# ESP_LoRa_Thermal_V1_62.net
KiCad netlist of a schematic drawn in EAGLE
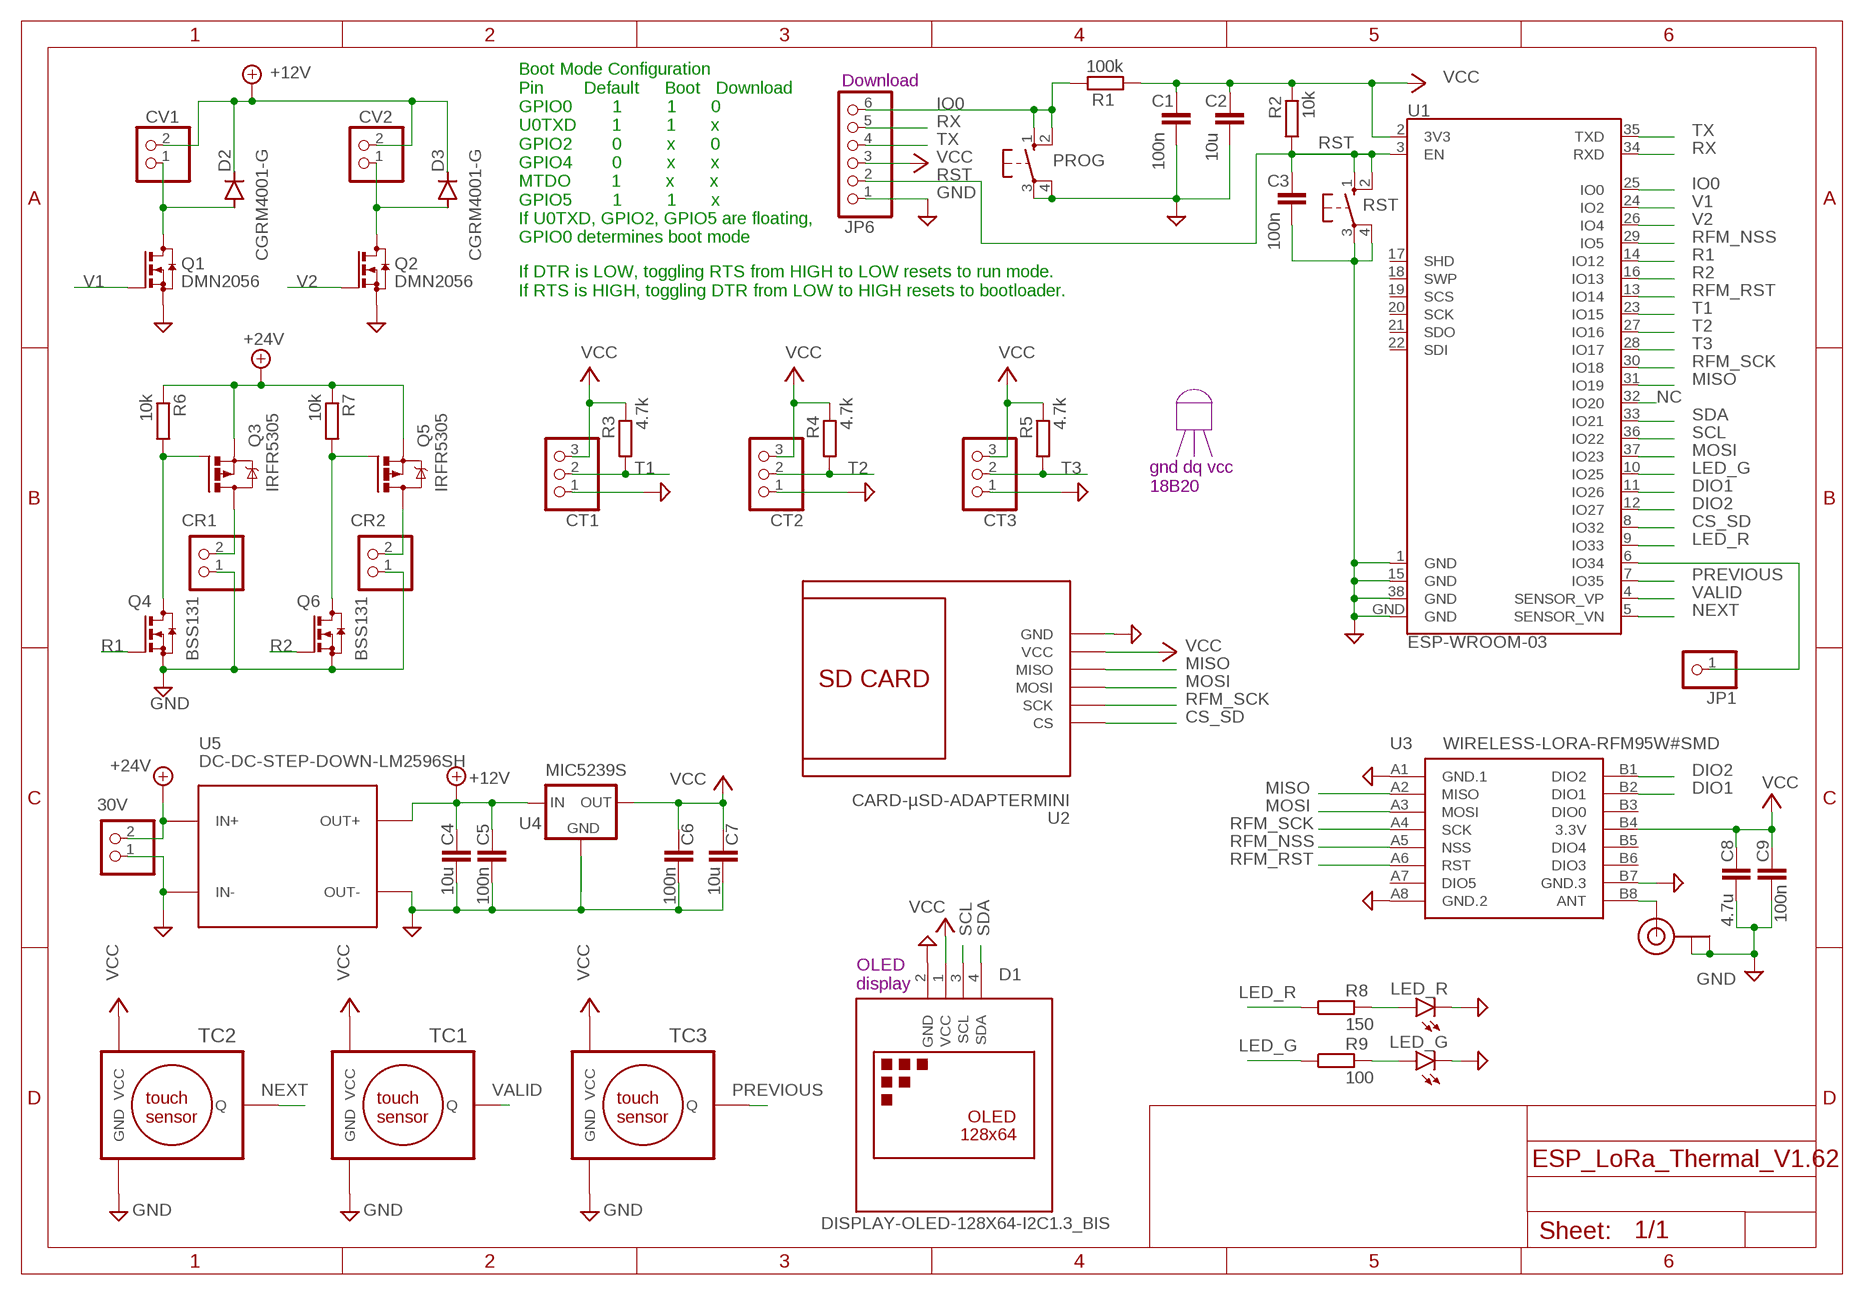
[diagram p0: schematic, sheet 1]

(export (version "E")
  (design (tool "Eeschema 10.0.6"))
  (components
    (comp (ref "30V")
      (value "PINHD-1X2")
      (footprint "eagle-import:1X02")
      (libsource (lib "eagle-import") (part "PINHD-1X2"))
    )
    (comp (ref "C1")
      (value "100n")
      (footprint "eagle-import:C1206")
      (libsource (lib "eagle-import") (part "CC1206"))
    )
    (comp (ref "C2")
      (value "10u")
      (footprint "eagle-import:C1206")
      (libsource (lib "eagle-import") (part "CC1206"))
    )
    (comp (ref "C3")
      (value "100n")
      (footprint "eagle-import:C1206")
      (libsource (lib "eagle-import") (part "CC1206"))
    )
    (comp (ref "C4")
      (value "10u")
      (footprint "eagle-import:C1206")
      (libsource (lib "eagle-import") (part "CC1206"))
    )
    (comp (ref "C5")
      (value "100n")
      (footprint "eagle-import:C1206")
      (libsource (lib "eagle-import") (part "CC1206"))
    )
    (comp (ref "C6")
      (value "100n")
      (footprint "eagle-import:C1206")
      (libsource (lib "eagle-import") (part "CC1206"))
    )
    (comp (ref "C7")
      (value "10u")
      (footprint "eagle-import:C1206")
      (libsource (lib "eagle-import") (part "CC1206"))
    )
    (comp (ref "C8")
      (value "4.7u")
      (footprint "eagle-import:C1206")
      (libsource (lib "eagle-import") (part "CC1206"))
    )
    (comp (ref "C9")
      (value "100n")
      (footprint "eagle-import:C1206")
      (libsource (lib "eagle-import") (part "CC1206"))
    )
    (comp (ref "CR1")
      (value "PINHD-1X2")
      (footprint "eagle-import:1X02")
      (libsource (lib "eagle-import") (part "PINHD-1X2"))
    )
    (comp (ref "CR2")
      (value "PINHD-1X2")
      (footprint "eagle-import:1X02")
      (libsource (lib "eagle-import") (part "PINHD-1X2"))
    )
    (comp (ref "CT1")
      (value "PINHD-1X3")
      (footprint "eagle-import:1X03")
      (libsource (lib "eagle-import") (part "PINHD-1X3"))
    )
    (comp (ref "CT2")
      (value "PINHD-1X3")
      (footprint "eagle-import:1X03")
      (libsource (lib "eagle-import") (part "PINHD-1X3"))
    )
    (comp (ref "CT3")
      (value "PINHD-1X3")
      (footprint "eagle-import:1X03")
      (libsource (lib "eagle-import") (part "PINHD-1X3"))
    )
    (comp (ref "CV1")
      (value "PINHD-1X2")
      (footprint "eagle-import:1X02")
      (libsource (lib "eagle-import") (part "PINHD-1X2"))
    )
    (comp (ref "CV2")
      (value "PINHD-1X2")
      (footprint "eagle-import:1X02")
      (libsource (lib "eagle-import") (part "PINHD-1X2"))
    )
    (comp (ref "D1")
      (value "DISPLAY-OLED-128X64-I2C1.3_BIS")
      (footprint "eagle-import:DISPLAY-OLED-128X64-1.3-I2C_BIS")
      (libsource (lib "eagle-import") (part "DISPLAY-OLED-128X64-I2C1.3_BIS"))
    )
    (comp (ref "D2")
      (value "CGRM4001-G")
      (footprint "eagle-import:SOD-123_MINI-SMA")
      (libsource (lib "eagle-import") (part "CGRM400-G1"))
    )
    (comp (ref "D3")
      (value "CGRM4001-G")
      (footprint "eagle-import:SOD-123_MINI-SMA")
      (libsource (lib "eagle-import") (part "CGRM400-G1"))
    )
    (comp (ref "J1")
      (value "U.FL")
      (footprint "eagle-import:U.FL")
      (libsource (lib "eagle-import") (part "U.FL"))
    )
    (comp (ref "JP1")
      (value "PINHD-1X1")
      (footprint "eagle-import:1X01")
      (libsource (lib "eagle-import") (part "PINHD-1X1"))
    )
    (comp (ref "JP6")
      (value "PINHD-1X6")
      (footprint "eagle-import:1X06")
      (libsource (lib "eagle-import") (part "PINHD-1X6"))
    )
    (comp (ref "LED_G")
      (value "LEDSMT1206")
      (footprint "eagle-import:1206")
      (libsource (lib "eagle-import") (part "LEDSMT1206"))
    )
    (comp (ref "LED_R")
      (value "LEDSMT1206")
      (footprint "eagle-import:1206")
      (libsource (lib "eagle-import") (part "LEDSMT1206"))
    )
    (comp (ref "PROG")
      (value "10-XX")
      (footprint "eagle-import:B3F-10XX")
      (fields (field (name "MPN") "B3F-1000"))
      (libsource (lib "eagle-import") (part "10-XX"))
    )
    (comp (ref "Q1")
      (value "DMN2056")
      (footprint "eagle-import:SOT23")
      (libsource (lib "eagle-import") (part "DMN2056"))
    )
    (comp (ref "Q2")
      (value "DMN2056")
      (footprint "eagle-import:SOT23")
      (libsource (lib "eagle-import") (part "DMN2056"))
    )
    (comp (ref "Q3")
      (value "IRFR5305")
      (footprint "eagle-import:D-PAK_TO252AA")
      (libsource (lib "eagle-import") (part "IRF?5305R"))
    )
    (comp (ref "Q4")
      (value "BSS131")
      (footprint "eagle-import:SOT23")
      (libsource (lib "eagle-import") (part "BSS131"))
    )
    (comp (ref "Q5")
      (value "IRFR5305")
      (footprint "eagle-import:D-PAK_TO252AA")
      (libsource (lib "eagle-import") (part "IRF?5305R"))
    )
    (comp (ref "Q6")
      (value "BSS131")
      (footprint "eagle-import:SOT23")
      (libsource (lib "eagle-import") (part "BSS131"))
    )
    (comp (ref "R1")
      (value "100k")
      (footprint "eagle-import:R1206")
      (libsource (lib "eagle-import") (part "RR1206"))
    )
    (comp (ref "R2")
      (value "10k")
      (footprint "eagle-import:R1206")
      (libsource (lib "eagle-import") (part "RR1206"))
    )
    (comp (ref "R3")
      (value "4.7k")
      (footprint "eagle-import:R1206")
      (libsource (lib "eagle-import") (part "RR1206"))
    )
    (comp (ref "R4")
      (value "4.7k")
      (footprint "eagle-import:R1206")
      (libsource (lib "eagle-import") (part "RR1206"))
    )
    (comp (ref "R5")
      (value "4.7k")
      (footprint "eagle-import:R1206")
      (libsource (lib "eagle-import") (part "RR1206"))
    )
    (comp (ref "R6")
      (value "10k")
      (footprint "eagle-import:R1206")
      (libsource (lib "eagle-import") (part "R-EU_R1206"))
    )
    (comp (ref "R7")
      (value "10k")
      (footprint "eagle-import:R1206")
      (libsource (lib "eagle-import") (part "R-EU_R1206"))
    )
    (comp (ref "R8")
      (value "150")
      (footprint "eagle-import:R1206")
      (libsource (lib "eagle-import") (part "RR1206"))
    )
    (comp (ref "R9")
      (value "100")
      (footprint "eagle-import:R1206")
      (libsource (lib "eagle-import") (part "RR1206"))
    )
    (comp (ref "RST")
      (value "10-XX")
      (footprint "eagle-import:B3F-10XX")
      (fields (field (name "MPN") "B3F-1000"))
      (libsource (lib "eagle-import") (part "10-XX"))
    )
    (comp (ref "TC1")
      (value "TTP223R_H")
      (footprint "eagle-import:TTP233RED_H")
      (libsource (lib "eagle-import") (part "TTP223R_H"))
    )
    (comp (ref "TC2")
      (value "TTP223R_H")
      (footprint "eagle-import:TTP233RED_H")
      (libsource (lib "eagle-import") (part "TTP223R_H"))
    )
    (comp (ref "TC3")
      (value "TTP223R_H")
      (footprint "eagle-import:TTP233RED_H")
      (libsource (lib "eagle-import") (part "TTP223R_H"))
    )
    (comp (ref "U1")
      (value "ESP-WROOM-03")
      (footprint "eagle-import:ESP-WROOM-03")
      (libsource (lib "eagle-import") (part "ESP-WROOM-03"))
    )
    (comp (ref "U2")
      (value "CARD-µSD-ADAPTERMINI")
      (footprint "eagle-import:CARD-MINI--µSD-READER")
      (libsource (lib "eagle-import") (part "CARD-µSD-ADAPTERMINI"))
    )
    (comp (ref "U3")
      (value "WIRELESS-LORA-RFM95W#SMD")
      (footprint "eagle-import:WIRELESS-LORA-RFM95W#SMD")
      (libsource (lib "eagle-import") (part "WIRELESS-LORA-RFM95W#SMD"))
    )
    (comp (ref "U4")
      (value "MIC5239S")
      (footprint "eagle-import:SOT223")
      (libsource (lib "eagle-import") (part "MIC5239S"))
    )
    (comp (ref "U5")
      (value "DC-DC-STEP-DOWN-LM2596SH")
      (footprint "eagle-import:DC-DC-STEP-DOWN-LM2596-SH")
      (libsource (lib "eagle-import") (part "DC-DC-STEP-DOWN-LM2596SH"))
    )
  )
  (nets
    (net (code "1") (name "+12V") (class "Default")
      (node (ref "C4") (pin "1") (pinfunction "1_1") (pintype "passive"))
      (node (ref "C5") (pin "1") (pinfunction "1_1") (pintype "passive"))
      (node (ref "CV1") (pin "2") (pinfunction "2_2") (pintype "passive"))
      (node (ref "CV2") (pin "2") (pinfunction "2_2") (pintype "passive"))
      (node (ref "D2") (pin "C") (pinfunction "C_C") (pintype "passive"))
      (node (ref "D3") (pin "C") (pinfunction "C_C") (pintype "passive"))
      (node (ref "U4") (pin "1") (pinfunction "IN_1") (pintype "input"))
      (node (ref "U5") (pin "OUT+") (pinfunction "OUT+_OUT+") (pintype "bidirectional"))
    )
    (net (code "2") (name "+24V") (class "Default")
      (node (ref "30V") (pin "2") (pinfunction "2_2") (pintype "passive"))
      (node (ref "Q3") (pin "3") (pinfunction "S_3") (pintype "passive"))
      (node (ref "Q5") (pin "3") (pinfunction "S_3") (pintype "passive"))
      (node (ref "R6") (pin "1") (pinfunction "1_1") (pintype "passive"))
      (node (ref "R7") (pin "1") (pinfunction "1_1") (pintype "passive"))
      (node (ref "U5") (pin "IN+") (pinfunction "IN+_IN+") (pintype "bidirectional"))
    )
    (net (code "3") (name "/CS_SD") (class "Default")
      (node (ref "U1") (pin "8") (pinfunction "IO32_8") (pintype "bidirectional"))
      (node (ref "U2") (pin "CS") (pinfunction "CS_CS") (pintype "bidirectional"))
    )
    (net (code "4") (name "/DIO1") (class "Default")
      (node (ref "U1") (pin "11") (pinfunction "IO26_11") (pintype "bidirectional"))
      (node (ref "U3") (pin "B2") (pinfunction "DIO1_B2") (pintype "bidirectional"))
    )
    (net (code "5") (name "/DIO2") (class "Default")
      (node (ref "U1") (pin "12") (pinfunction "IO27_12") (pintype "bidirectional"))
      (node (ref "U3") (pin "B1") (pinfunction "DIO2_B1") (pintype "bidirectional"))
    )
    (net (code "6") (name "/IO0") (class "Default")
      (node (ref "JP6") (pin "6") (pinfunction "6_6") (pintype "passive"))
      (node (ref "PROG") (pin "1") (pinfunction "S_1") (pintype "passive"))
      (node (ref "PROG") (pin "2") (pinfunction "S1_2") (pintype "passive"))
      (node (ref "R1") (pin "2") (pinfunction "2_2") (pintype "passive"))
      (node (ref "U1") (pin "25") (pinfunction "IO0_25") (pintype "bidirectional"))
    )
    (net (code "7") (name "/LED_G") (class "Default")
      (node (ref "R9") (pin "1") (pinfunction "1_1") (pintype "passive"))
      (node (ref "U1") (pin "10") (pinfunction "IO25_10") (pintype "bidirectional"))
    )
    (net (code "8") (name "/LED_R") (class "Default")
      (node (ref "R8") (pin "1") (pinfunction "1_1") (pintype "passive"))
      (node (ref "U1") (pin "9") (pinfunction "IO33_9") (pintype "bidirectional"))
    )
    (net (code "9") (name "/MISO") (class "Default")
      (node (ref "U1") (pin "31") (pinfunction "IO19_31") (pintype "bidirectional"))
      (node (ref "U2") (pin "MISO") (pinfunction "MISO_MISO") (pintype "bidirectional"))
      (node (ref "U3") (pin "A2") (pinfunction "MISO_A2") (pintype "bidirectional"))
    )
    (net (code "10") (name "/MOSI") (class "Default")
      (node (ref "U1") (pin "37") (pinfunction "IO23_37") (pintype "bidirectional"))
      (node (ref "U2") (pin "MOSI") (pinfunction "MOSI_MOSI") (pintype "bidirectional"))
      (node (ref "U3") (pin "A3") (pinfunction "MOSI_A3") (pintype "bidirectional"))
    )
    (net (code "11") (name "/NC") (class "Default")
      (node (ref "U1") (pin "32") (pinfunction "IO20_32") (pintype "bidirectional"))
    )
    (net (code "12") (name "/NEXT") (class "Default")
      (node (ref "TC2") (pin "P$2") (pinfunction "Q_P$2") (pintype "power_in"))
      (node (ref "U1") (pin "5") (pinfunction "SENSOR_VN_5") (pintype "bidirectional"))
    )
    (net (code "13") (name "/PREVIOUS") (class "Default")
      (node (ref "TC3") (pin "P$2") (pinfunction "Q_P$2") (pintype "power_in"))
      (node (ref "U1") (pin "7") (pinfunction "IO35_7") (pintype "bidirectional"))
    )
    (net (code "14") (name "/R1") (class "Default")
      (node (ref "Q4") (pin "1") (pinfunction "G_1") (pintype "passive"))
      (node (ref "U1") (pin "14") (pinfunction "IO12_14") (pintype "bidirectional"))
    )
    (net (code "15") (name "/R2") (class "Default")
      (node (ref "Q6") (pin "1") (pinfunction "G_1") (pintype "passive"))
      (node (ref "U1") (pin "16") (pinfunction "IO13_16") (pintype "bidirectional"))
    )
    (net (code "16") (name "/RFM_NSS") (class "Default")
      (node (ref "U1") (pin "29") (pinfunction "IO5_29") (pintype "bidirectional"))
      (node (ref "U3") (pin "A5") (pinfunction "NSS_A5") (pintype "bidirectional"))
    )
    (net (code "17") (name "/RFM_RST") (class "Default")
      (node (ref "U1") (pin "13") (pinfunction "IO14_13") (pintype "bidirectional"))
      (node (ref "U3") (pin "A6") (pinfunction "RST_A6") (pintype "bidirectional"))
    )
    (net (code "18") (name "/RFM_SCK") (class "Default")
      (node (ref "U1") (pin "30") (pinfunction "IO18_30") (pintype "bidirectional"))
      (node (ref "U2") (pin "SCK") (pinfunction "SCK_SCK") (pintype "bidirectional"))
      (node (ref "U3") (pin "A4") (pinfunction "SCK_A4") (pintype "bidirectional"))
    )
    (net (code "19") (name "/RST") (class "Default")
      (node (ref "C3") (pin "1") (pinfunction "1_1") (pintype "passive"))
      (node (ref "JP6") (pin "2") (pinfunction "2_2") (pintype "passive"))
      (node (ref "R2") (pin "1") (pinfunction "1_1") (pintype "passive"))
      (node (ref "RST") (pin "1") (pinfunction "S_1") (pintype "passive"))
      (node (ref "RST") (pin "2") (pinfunction "S1_2") (pintype "passive"))
      (node (ref "U1") (pin "3") (pinfunction "EN_3") (pintype "bidirectional"))
    )
    (net (code "20") (name "/RX") (class "Default")
      (node (ref "JP6") (pin "5") (pinfunction "5_5") (pintype "passive"))
      (node (ref "U1") (pin "34") (pinfunction "RXD_34") (pintype "bidirectional"))
    )
    (net (code "21") (name "/SCL") (class "Default")
      (node (ref "D1") (pin "3") (pinfunction "SCL_3") (pintype "bidirectional"))
      (node (ref "U1") (pin "36") (pinfunction "IO22_36") (pintype "bidirectional"))
    )
    (net (code "22") (name "/SDA") (class "Default")
      (node (ref "D1") (pin "4") (pinfunction "SDA_4") (pintype "bidirectional"))
      (node (ref "U1") (pin "33") (pinfunction "IO21_33") (pintype "bidirectional"))
    )
    (net (code "23") (name "/T1") (class "Default")
      (node (ref "CT1") (pin "2") (pinfunction "2_2") (pintype "passive"))
      (node (ref "R3") (pin "1") (pinfunction "1_1") (pintype "passive"))
      (node (ref "U1") (pin "23") (pinfunction "IO15_23") (pintype "bidirectional"))
    )
    (net (code "24") (name "/T2") (class "Default")
      (node (ref "CT2") (pin "2") (pinfunction "2_2") (pintype "passive"))
      (node (ref "R4") (pin "1") (pinfunction "1_1") (pintype "passive"))
      (node (ref "U1") (pin "27") (pinfunction "IO16_27") (pintype "bidirectional"))
    )
    (net (code "25") (name "/T3") (class "Default")
      (node (ref "CT3") (pin "2") (pinfunction "2_2") (pintype "passive"))
      (node (ref "R5") (pin "1") (pinfunction "1_1") (pintype "passive"))
      (node (ref "U1") (pin "28") (pinfunction "IO17_28") (pintype "bidirectional"))
    )
    (net (code "26") (name "/TX") (class "Default")
      (node (ref "JP6") (pin "4") (pinfunction "4_4") (pintype "passive"))
      (node (ref "U1") (pin "35") (pinfunction "TXD_35") (pintype "bidirectional"))
    )
    (net (code "27") (name "/V1") (class "Default")
      (node (ref "Q1") (pin "1") (pinfunction "G_1") (pintype "passive"))
      (node (ref "U1") (pin "24") (pinfunction "IO2_24") (pintype "bidirectional"))
    )
    (net (code "28") (name "/V2") (class "Default")
      (node (ref "Q2") (pin "1") (pinfunction "G_1") (pintype "passive"))
      (node (ref "U1") (pin "26") (pinfunction "IO4_26") (pintype "bidirectional"))
    )
    (net (code "29") (name "/VALID") (class "Default")
      (node (ref "TC1") (pin "P$2") (pinfunction "Q_P$2") (pintype "power_in"))
      (node (ref "U1") (pin "4") (pinfunction "SENSOR_VP_4") (pintype "bidirectional"))
    )
    (net (code "30") (name "GND") (class "Default")
      (node (ref "30V") (pin "1") (pinfunction "1_1") (pintype "passive"))
      (node (ref "C1") (pin "2") (pinfunction "2_2") (pintype "passive"))
      (node (ref "C2") (pin "2") (pinfunction "2_2") (pintype "passive"))
      (node (ref "C3") (pin "2") (pinfunction "2_2") (pintype "passive"))
      (node (ref "C4") (pin "2") (pinfunction "2_2") (pintype "passive"))
      (node (ref "C5") (pin "2") (pinfunction "2_2") (pintype "passive"))
      (node (ref "C6") (pin "2") (pinfunction "2_2") (pintype "passive"))
      (node (ref "C7") (pin "2") (pinfunction "2_2") (pintype "passive"))
      (node (ref "C8") (pin "2") (pinfunction "2_2") (pintype "passive"))
      (node (ref "C9") (pin "2") (pinfunction "2_2") (pintype "passive"))
      (node (ref "CR1") (pin "1") (pinfunction "1_1") (pintype "passive"))
      (node (ref "CR2") (pin "1") (pinfunction "1_1") (pintype "passive"))
      (node (ref "CT1") (pin "1") (pinfunction "1_1") (pintype "passive"))
      (node (ref "CT2") (pin "1") (pinfunction "1_1") (pintype "passive"))
      (node (ref "CT3") (pin "1") (pinfunction "1_1") (pintype "passive"))
      (node (ref "D1") (pin "2") (pinfunction "GND_2") (pintype "power_in"))
      (node (ref "J1") (pin "1") (pinfunction "GND_1") (pintype "passive"))
      (node (ref "J1") (pin "2") (pinfunction "GND_2") (pintype "passive"))
      (node (ref "JP6") (pin "1") (pinfunction "1_1") (pintype "passive"))
      (node (ref "LED_G") (pin "C") (pinfunction "C_C") (pintype "passive"))
      (node (ref "LED_R") (pin "C") (pinfunction "C_C") (pintype "passive"))
      (node (ref "PROG") (pin "3") (pinfunction "P_3") (pintype "passive"))
      (node (ref "PROG") (pin "4") (pinfunction "P1_4") (pintype "passive"))
      (node (ref "Q1") (pin "2") (pinfunction "S_2") (pintype "passive"))
      (node (ref "Q2") (pin "2") (pinfunction "S_2") (pintype "passive"))
      (node (ref "Q4") (pin "2") (pinfunction "S_2") (pintype "passive"))
      (node (ref "Q6") (pin "2") (pinfunction "S_2") (pintype "passive"))
      (node (ref "RST") (pin "3") (pinfunction "P_3") (pintype "passive"))
      (node (ref "RST") (pin "4") (pinfunction "P1_4") (pintype "passive"))
      (node (ref "TC1") (pin "P$3") (pinfunction "GND_P$3") (pintype "power_in"))
      (node (ref "TC2") (pin "P$3") (pinfunction "GND_P$3") (pintype "power_in"))
      (node (ref "TC3") (pin "P$3") (pinfunction "GND_P$3") (pintype "power_in"))
      (node (ref "U1") (pin "1") (pinfunction "GND_1") (pintype "bidirectional"))
      (node (ref "U1") (pin "15") (pinfunction "GND_15") (pintype "bidirectional"))
      (node (ref "U1") (pin "38") (pinfunction "GND_38") (pintype "bidirectional"))
      (node (ref "U1") (pin "GND") (pinfunction "GND_GND") (pintype "bidirectional"))
      (node (ref "U2") (pin "GND") (pinfunction "GND_GND") (pintype "power_in"))
      (node (ref "U3") (pin "A1") (pinfunction "GND.1_A1") (pintype "power_in"))
      (node (ref "U3") (pin "A8") (pinfunction "GND.2_A8") (pintype "power_in"))
      (node (ref "U3") (pin "B7") (pinfunction "GND.3_B7") (pintype "power_in"))
      (node (ref "U4") (pin "2") (pinfunction "GND_2") (pintype "passive"))
      (node (ref "U4") (pin "4") (pinfunction "GND_4") (pintype "passive"))
      (node (ref "U5") (pin "IN-") (pinfunction "IN-_IN-") (pintype "bidirectional"))
      (node (ref "U5") (pin "OUT-") (pinfunction "OUT-_OUT-") (pintype "bidirectional"))
    )
    (net (code "31") (name "Net-(J1-SIGNAL)") (class "Default")
      (node (ref "J1") (pin "3") (pinfunction "SIGNAL_3") (pintype "passive"))
      (node (ref "U3") (pin "B8") (pinfunction "ANT_B8") (pintype "passive"))
    )
    (net (code "32") (name "Net-(LED_G-PadA)") (class "Default")
      (node (ref "LED_G") (pin "A") (pinfunction "A_A") (pintype "passive"))
      (node (ref "R9") (pin "2") (pinfunction "2_2") (pintype "passive"))
    )
    (net (code "33") (name "Net-(LED_R-PadA)") (class "Default")
      (node (ref "LED_R") (pin "A") (pinfunction "A_A") (pintype "passive"))
      (node (ref "R8") (pin "2") (pinfunction "2_2") (pintype "passive"))
    )
    (net (code "34") (name "Net-(Q1-D)") (class "Default")
      (node (ref "CV1") (pin "1") (pinfunction "1_1") (pintype "passive"))
      (node (ref "D2") (pin "A") (pinfunction "A_A") (pintype "passive"))
      (node (ref "Q1") (pin "3") (pinfunction "D_3") (pintype "passive"))
    )
    (net (code "35") (name "Net-(Q2-D)") (class "Default")
      (node (ref "CV2") (pin "1") (pinfunction "1_1") (pintype "passive"))
      (node (ref "D3") (pin "A") (pinfunction "A_A") (pintype "passive"))
      (node (ref "Q2") (pin "3") (pinfunction "D_3") (pintype "passive"))
    )
    (net (code "36") (name "Net-(Q3-D)") (class "Default")
      (node (ref "CR1") (pin "2") (pinfunction "2_2") (pintype "passive"))
      (node (ref "Q3") (pin "4") (pinfunction "D_4") (pintype "passive"))
    )
    (net (code "37") (name "Net-(Q3-G)") (class "Default")
      (node (ref "Q3") (pin "1") (pinfunction "G_1") (pintype "passive"))
      (node (ref "Q4") (pin "3") (pinfunction "D_3") (pintype "passive"))
      (node (ref "R6") (pin "2") (pinfunction "2_2") (pintype "passive"))
    )
    (net (code "38") (name "Net-(Q5-D)") (class "Default")
      (node (ref "CR2") (pin "2") (pinfunction "2_2") (pintype "passive"))
      (node (ref "Q5") (pin "4") (pinfunction "D_4") (pintype "passive"))
    )
    (net (code "39") (name "Net-(Q5-G)") (class "Default")
      (node (ref "Q5") (pin "1") (pinfunction "G_1") (pintype "passive"))
      (node (ref "Q6") (pin "3") (pinfunction "D_3") (pintype "passive"))
      (node (ref "R7") (pin "2") (pinfunction "2_2") (pintype "passive"))
    )
    (net (code "40") (name "Net-(U1-IO34)") (class "Default")
      (node (ref "JP1") (pin "1") (pinfunction "1_1") (pintype "passive"))
      (node (ref "U1") (pin "6") (pinfunction "IO34_6") (pintype "bidirectional"))
    )
    (net (code "41") (name "VCC") (class "Default")
      (node (ref "C1") (pin "1") (pinfunction "1_1") (pintype "passive"))
      (node (ref "C2") (pin "1") (pinfunction "1_1") (pintype "passive"))
      (node (ref "C6") (pin "1") (pinfunction "1_1") (pintype "passive"))
      (node (ref "C7") (pin "1") (pinfunction "1_1") (pintype "passive"))
      (node (ref "C8") (pin "1") (pinfunction "1_1") (pintype "passive"))
      (node (ref "C9") (pin "1") (pinfunction "1_1") (pintype "passive"))
      (node (ref "CT1") (pin "3") (pinfunction "3_3") (pintype "passive"))
      (node (ref "CT2") (pin "3") (pinfunction "3_3") (pintype "passive"))
      (node (ref "CT3") (pin "3") (pinfunction "3_3") (pintype "passive"))
      (node (ref "D1") (pin "1") (pinfunction "VCC_1") (pintype "power_in"))
      (node (ref "JP6") (pin "3") (pinfunction "3_3") (pintype "passive"))
      (node (ref "R1") (pin "1") (pinfunction "1_1") (pintype "passive"))
      (node (ref "R2") (pin "2") (pinfunction "2_2") (pintype "passive"))
      (node (ref "R3") (pin "2") (pinfunction "2_2") (pintype "passive"))
      (node (ref "R4") (pin "2") (pinfunction "2_2") (pintype "passive"))
      (node (ref "R5") (pin "2") (pinfunction "2_2") (pintype "passive"))
      (node (ref "TC1") (pin "P$1") (pinfunction "VCC_P$1") (pintype "power_in"))
      (node (ref "TC2") (pin "P$1") (pinfunction "VCC_P$1") (pintype "power_in"))
      (node (ref "TC3") (pin "P$1") (pinfunction "VCC_P$1") (pintype "power_in"))
      (node (ref "U1") (pin "2") (pinfunction "3V3_2") (pintype "bidirectional"))
      (node (ref "U2") (pin "VCC") (pinfunction "VCC_VCC") (pintype "power_in"))
      (node (ref "U3") (pin "B4") (pinfunction "3.3V_B4") (pintype "power_in"))
      (node (ref "U4") (pin "3") (pinfunction "OUT_3") (pintype "passive"))
    )
    (net (code "42") (name "unconnected-(U1-SCK-Pad20)") (class "Default")
      (node (ref "U1") (pin "20") (pinfunction "SCK_20") (pintype "bidirectional"))
    )
    (net (code "43") (name "unconnected-(U1-SCS-Pad19)") (class "Default")
      (node (ref "U1") (pin "19") (pinfunction "SCS_19") (pintype "bidirectional"))
    )
    (net (code "44") (name "unconnected-(U1-SDI-Pad22)") (class "Default")
      (node (ref "U1") (pin "22") (pinfunction "SDI_22") (pintype "bidirectional"))
    )
    (net (code "45") (name "unconnected-(U1-SDO-Pad21)") (class "Default")
      (node (ref "U1") (pin "21") (pinfunction "SDO_21") (pintype "bidirectional"))
    )
    (net (code "46") (name "unconnected-(U1-SHD-Pad17)") (class "Default")
      (node (ref "U1") (pin "17") (pinfunction "SHD_17") (pintype "bidirectional"))
    )
    (net (code "47") (name "unconnected-(U1-SWP-Pad18)") (class "Default")
      (node (ref "U1") (pin "18") (pinfunction "SWP_18") (pintype "bidirectional"))
    )
    (net (code "48") (name "unconnected-(U3-DIO0-PadB3)") (class "Default")
      (node (ref "U3") (pin "B3") (pinfunction "DIO0_B3") (pintype "bidirectional"))
    )
    (net (code "49") (name "unconnected-(U3-DIO3-PadB6)") (class "Default")
      (node (ref "U3") (pin "B6") (pinfunction "DIO3_B6") (pintype "bidirectional"))
    )
    (net (code "50") (name "unconnected-(U3-DIO4-PadB5)") (class "Default")
      (node (ref "U3") (pin "B5") (pinfunction "DIO4_B5") (pintype "bidirectional"))
    )
    (net (code "51") (name "unconnected-(U3-DIO5-PadA7)") (class "Default")
      (node (ref "U3") (pin "A7") (pinfunction "DIO5_A7") (pintype "bidirectional"))
    )
  )
)
